# zxclone.net
KiCad netlist of a schematic drawn in EAGLE
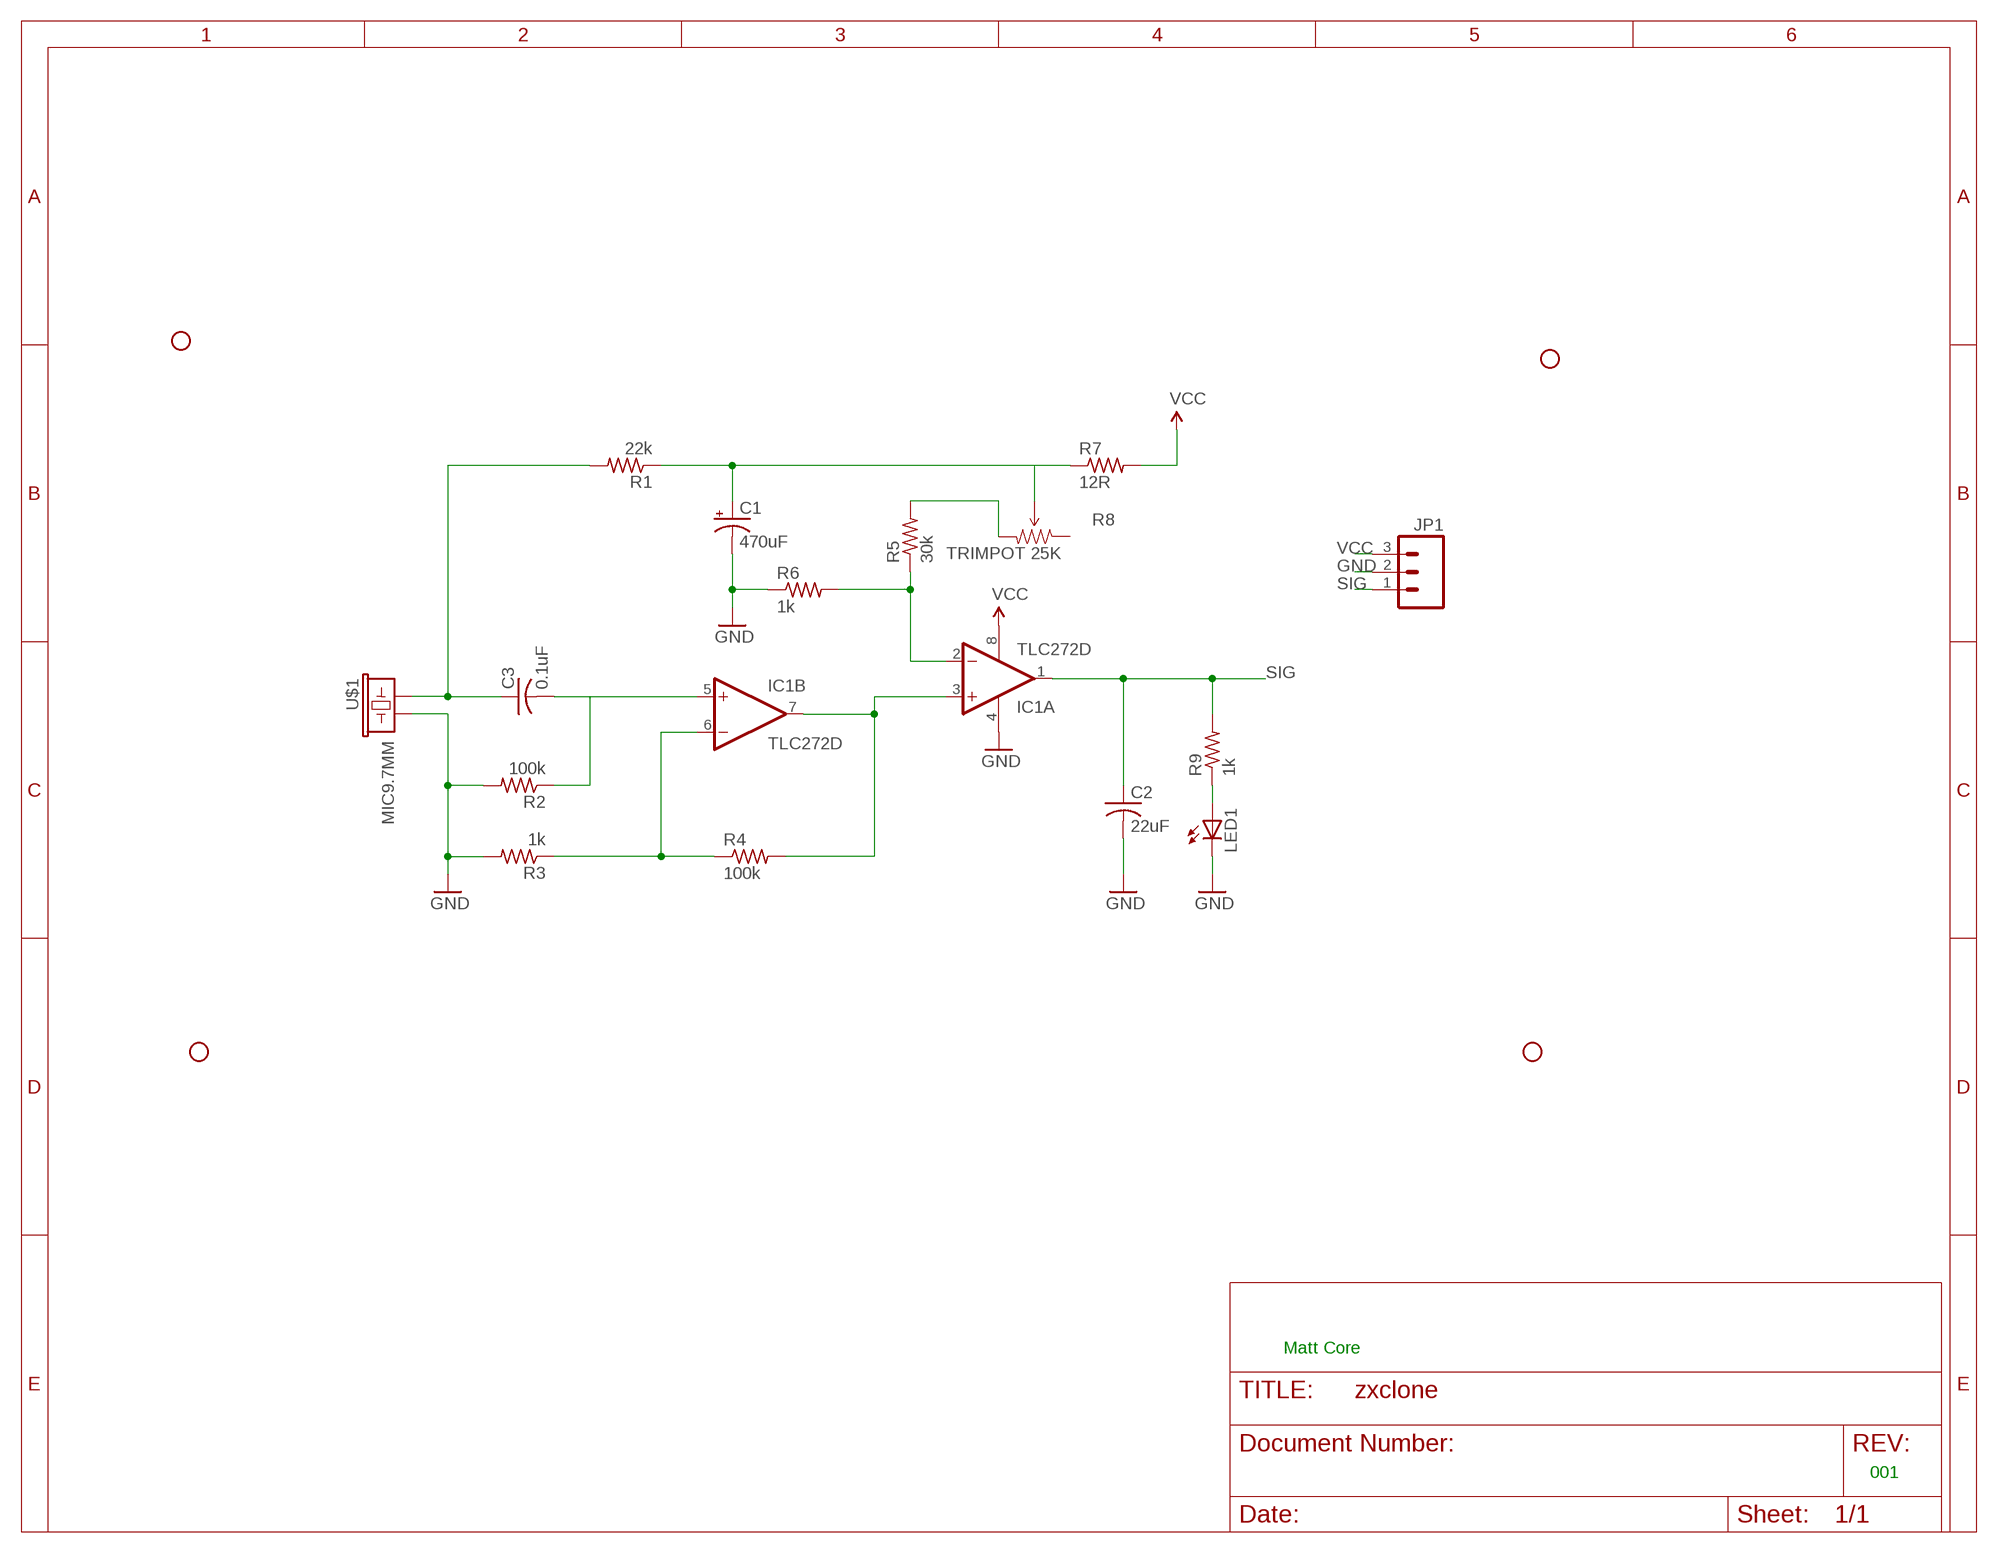
[diagram p0: schematic, sheet 1]

(export (version "E")
  (design (tool "Eeschema 10.0.6"))
  (components
    (comp (ref "C1")
      (value "470uF")
      (footprint "eagle-import:E2,5-7")
      (libsource (lib "eagle-import") (part "CPOL-USE2.5-7"))
    )
    (comp (ref "C2")
      (value "22uF")
      (footprint "eagle-import:C1206")
      (libsource (lib "eagle-import") (part "C-USC1206"))
    )
    (comp (ref "C3")
      (value "0.1uF")
      (footprint "eagle-import:C1005")
      (libsource (lib "eagle-import") (part "C-USC1005"))
    )
    (comp (ref "IC1")
      (value "TLC272D")
      (footprint "eagle-import:SO08")
      (libsource (lib "eagle-import") (part "TLC272D"))
    )
    (comp (ref "JP1")
      (value "M03PTH")
      (footprint "eagle-import:1X03")
      (libsource (lib "eagle-import") (part "M03PTH"))
    )
    (comp (ref "LED1")
      (value "LEDSML0603")
      (footprint "eagle-import:SML0603")
      (libsource (lib "eagle-import") (part "LEDSML0603"))
    )
    (comp (ref "R1")
      (value "22k")
      (footprint "eagle-import:R0402")
      (libsource (lib "eagle-import") (part "R-US_R0402"))
    )
    (comp (ref "R2")
      (value "100k")
      (footprint "eagle-import:R0402")
      (libsource (lib "eagle-import") (part "R-US_R0402"))
    )
    (comp (ref "R3")
      (value "1k")
      (footprint "eagle-import:R0402")
      (libsource (lib "eagle-import") (part "R-US_R0402"))
    )
    (comp (ref "R4")
      (value "100k")
      (footprint "eagle-import:R0402")
      (libsource (lib "eagle-import") (part "R-US_R0402"))
    )
    (comp (ref "R5")
      (value "30k")
      (footprint "eagle-import:R0402")
      (libsource (lib "eagle-import") (part "R-US_R0402"))
    )
    (comp (ref "R6")
      (value "1k")
      (footprint "eagle-import:R0402")
      (libsource (lib "eagle-import") (part "R-US_R0402"))
    )
    (comp (ref "R7")
      (value "12R")
      (footprint "eagle-import:R0805")
      (libsource (lib "eagle-import") (part "R-US_R0805"))
    )
    (comp (ref "R8")
      (value "TRIMPOT 25K")
      (footprint "eagle-import:TRIMPOT_TC33")
      (libsource (lib "eagle-import") (part "TRIMPOT-2"))
    )
    (comp (ref "R9")
      (value "1k")
      (footprint "eagle-import:R0402")
      (libsource (lib "eagle-import") (part "R-US_R0402"))
    )
    (comp (ref "STANDOFF1")
      (value "STAND-OFF")
      (footprint "eagle-import:STAND-OFF")
      (libsource (lib "eagle-import") (part "STAND-OFF"))
    )
    (comp (ref "STANDOFF2")
      (value "STAND-OFF")
      (footprint "eagle-import:STAND-OFF")
      (libsource (lib "eagle-import") (part "STAND-OFF"))
    )
    (comp (ref "STANDOFF3")
      (value "STAND-OFF")
      (footprint "eagle-import:STAND-OFF")
      (libsource (lib "eagle-import") (part "STAND-OFF"))
    )
    (comp (ref "STANDOFF4")
      (value "STAND-OFF")
      (footprint "eagle-import:STAND-OFF")
      (libsource (lib "eagle-import") (part "STAND-OFF"))
    )
    (comp (ref "U$1")
      (value "MIC9.7MM")
      (footprint "eagle-import:MIC-9.7MM")
      (libsource (lib "eagle-import") (part "MIC9.7MM"))
    )
  )
  (nets
    (net (code "1") (name "/SIG") (class "Default")
      (node (ref "C2") (pin "1") (pinfunction "1_1") (pintype "passive"))
      (node (ref "IC1") (pin "1") (pinfunction "OUT_1") (pintype "output"))
      (node (ref "JP1") (pin "1") (pinfunction "1_1") (pintype "passive"))
      (node (ref "R9") (pin "2") (pinfunction "2_2") (pintype "passive"))
    )
    (net (code "2") (name "GND") (class "Default")
      (node (ref "C1") (pin "-") (pinfunction "-_-") (pintype "passive"))
      (node (ref "C2") (pin "2") (pinfunction "2_2") (pintype "passive"))
      (node (ref "IC1") (pin "4") (pinfunction "V-_4") (pintype "power_in"))
      (node (ref "JP1") (pin "2") (pinfunction "2_2") (pintype "passive"))
      (node (ref "LED1") (pin "C") (pinfunction "C_C") (pintype "passive"))
      (node (ref "R2") (pin "2") (pinfunction "2_2") (pintype "passive"))
      (node (ref "R3") (pin "2") (pinfunction "2_2") (pintype "passive"))
      (node (ref "R6") (pin "1") (pinfunction "1_1") (pintype "passive"))
      (node (ref "U$1") (pin "2") (pinfunction "2_2") (pintype "passive"))
    )
    (net (code "3") (name "Net-(C3-Pad1)") (class "Default")
      (node (ref "C3") (pin "1") (pinfunction "1_1") (pintype "passive"))
      (node (ref "R1") (pin "2") (pinfunction "2_2") (pintype "passive"))
      (node (ref "U$1") (pin "1") (pinfunction "1_1") (pintype "passive"))
    )
    (net (code "4") (name "Net-(IC1A-+IN)") (class "Default")
      (node (ref "IC1") (pin "3") (pinfunction "+IN_3") (pintype "input"))
      (node (ref "IC1") (pin "7") (pinfunction "OUT_7") (pintype "output"))
      (node (ref "R4") (pin "2") (pinfunction "2_2") (pintype "passive"))
    )
    (net (code "5") (name "Net-(IC1A--IN)") (class "Default")
      (node (ref "IC1") (pin "2") (pinfunction "-IN_2") (pintype "input"))
      (node (ref "R5") (pin "1") (pinfunction "1_1") (pintype "passive"))
      (node (ref "R6") (pin "2") (pinfunction "2_2") (pintype "passive"))
    )
    (net (code "6") (name "Net-(IC1B-+IN)") (class "Default")
      (node (ref "C3") (pin "2") (pinfunction "2_2") (pintype "passive"))
      (node (ref "IC1") (pin "5") (pinfunction "+IN_5") (pintype "input"))
      (node (ref "R2") (pin "1") (pinfunction "1_1") (pintype "passive"))
    )
    (net (code "7") (name "Net-(IC1B--IN)") (class "Default")
      (node (ref "IC1") (pin "6") (pinfunction "-IN_6") (pintype "input"))
      (node (ref "R3") (pin "1") (pinfunction "1_1") (pintype "passive"))
      (node (ref "R4") (pin "1") (pinfunction "1_1") (pintype "passive"))
    )
    (net (code "8") (name "Net-(LED1-PadA)") (class "Default")
      (node (ref "LED1") (pin "A") (pinfunction "A_A") (pintype "passive"))
      (node (ref "R9") (pin "1") (pinfunction "1_1") (pintype "passive"))
    )
    (net (code "9") (name "Net-(R8-CW)") (class "Default")
      (node (ref "R5") (pin "2") (pinfunction "2_2") (pintype "passive"))
      (node (ref "R8") (pin "3") (pinfunction "CW_3") (pintype "passive"))
    )
    (net (code "10") (name "Net-(R8-WIPER)") (class "Default")
      (node (ref "C1") (pin "+") (pinfunction "+_+") (pintype "passive"))
      (node (ref "R1") (pin "1") (pinfunction "1_1") (pintype "passive"))
      (node (ref "R7") (pin "1") (pinfunction "1_1") (pintype "passive"))
      (node (ref "R8") (pin "2") (pinfunction "WIPER_2") (pintype "passive"))
    )
    (net (code "11") (name "VCC") (class "Default")
      (node (ref "IC1") (pin "8") (pinfunction "V+_8") (pintype "power_in"))
      (node (ref "JP1") (pin "3") (pinfunction "3_3") (pintype "passive"))
      (node (ref "R7") (pin "2") (pinfunction "2_2") (pintype "passive"))
    )
    (net (code "12") (name "unconnected-(R8-CCW-Pad1)") (class "Default")
      (node (ref "R8") (pin "1") (pinfunction "CCW_1") (pintype "passive"))
    )
  )
)
